# CAN_SN65HVD230D.net
KiCad netlist of a schematic drawn in Altium Designer
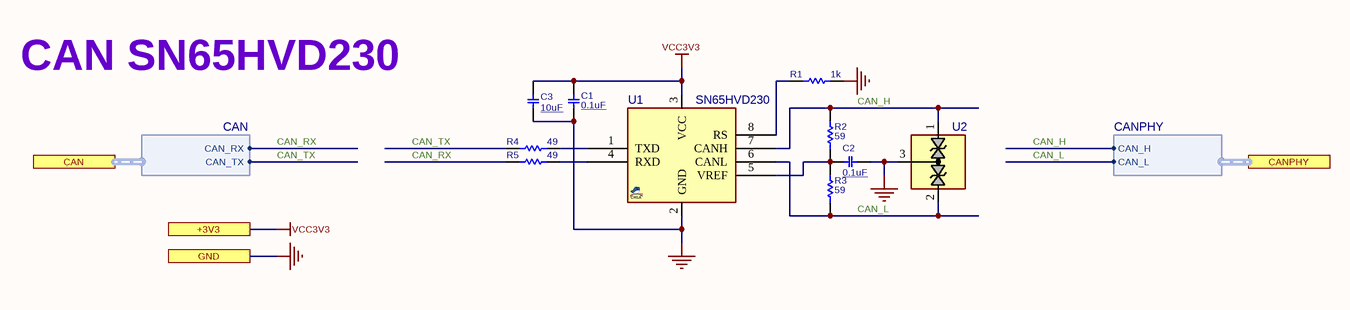
[diagram p0: CAN_SN65HVD230D.SchDoc]

(export (version "E")
  (design (tool "Eeschema 10.0.6"))
  (components
    (comp (ref "C1")
      (value "0.1uF")
      (footprint "C0603")
      (description "CAP, MLCC")
      (fields (field (name "MANF_P#") "MANF_PART#"))
      (libsource (lib "passive_smd") (part "CAP_SMD_MLCC_0402"))
    )
    (comp (ref "C2")
      (value "0.1uF")
      (footprint "C0603")
      (description "CAP, MLCC")
      (fields (field (name "MANF_P#") "MANF_PART#"))
      (libsource (lib "passive_smd") (part "CAP_SMD_MLCC_0402"))
    )
    (comp (ref "C3")
      (value "10uF")
      (footprint "C0603")
      (description "CAP, MLCC")
      (fields (field (name "MANF_P#") "MANF_PART#"))
      (libsource (lib "passive_smd") (part "CAP_SMD_MLCC_0402"))
    )
    (comp (ref "R1")
      (value "1k")
      (footprint "R0603")
      (description "RESISTOR, SMD")
      (libsource (lib "passive_smd") (part "RES_SMD_0402"))
    )
    (comp (ref "R2")
      (value "59")
      (footprint "R0603")
      (description "RESISTOR, SMD")
      (libsource (lib "passive_smd") (part "RES_SMD_0402"))
    )
    (comp (ref "R3")
      (value "59")
      (footprint "R0603")
      (description "RESISTOR, SMD")
      (libsource (lib "passive_smd") (part "RES_SMD_0402"))
    )
    (comp (ref "R4")
      (value "49")
      (footprint "R0603")
      (description "RESISTOR, SMD")
      (libsource (lib "passive_smd") (part "RES_SMD_0402"))
    )
    (comp (ref "R5")
      (value "49")
      (footprint "R0603")
      (description "RESISTOR, SMD")
      (libsource (lib "passive_smd") (part "RES_SMD_0402"))
    )
    (comp (ref "U1")
      (value "SN65HVD230")
      (footprint "SO_8")
      (description "CAN,  Transceivers, 3.3V (VDD)")
      (fields (field (name "MANF") "Texas Instruments") (field (name "MANF_P#") "SN65HVD230D, SN65HVD230QD"))
      (libsource (lib "can_phy") (part "SN65HVD230_SOP8"))
    )
    (comp (ref "U2")
      (value "CDSOT23-SM712")
      (footprint "SOT23_3")
      (description "TVS, ESD PROTECT, 2CH, 400W/17A PP, 7.5VBR, ±8KV ESDmin")
      (fields (field (name "MANF") "Bourns"))
      (libsource (lib "protect_tvs_esd_fuse") (part "TVS_X2_CDSOT23-SM712"))
    )
  )
  (nets
    (net (code "3") (name "/CAN_H") (class "Default")
      (node (ref "R2") (pin "2") (pinfunction "2_2") (pintype "passive"))
      (node (ref "U1") (pin "7") (pinfunction "CANH_7") (pintype "passive"))
      (node (ref "U2") (pin "1") (pinfunction "NC_1") (pintype "passive"))
    )
    (net (code "4") (name "/CAN_L") (class "Default")
      (node (ref "R3") (pin "1") (pinfunction "1_1") (pintype "passive"))
      (node (ref "U1") (pin "6") (pinfunction "CANL_6") (pintype "passive"))
      (node (ref "U2") (pin "2") (pinfunction "GND_2") (pintype "passive"))
    )
    (net (code "5") (name "/CAN_RX") (class "Default")
      (node (ref "R5") (pin "2") (pinfunction "2_2") (pintype "passive"))
    )
    (net (code "6") (name "/CAN_TX") (class "Default")
      (node (ref "R4") (pin "2") (pinfunction "2_2") (pintype "passive"))
    )
    (net (code "9") (name "GND") (class "Default")
      (node (ref "C1") (pin "1") (pinfunction "1_1") (pintype "passive"))
      (node (ref "C2") (pin "1") (pinfunction "1_1") (pintype "passive"))
      (node (ref "C3") (pin "2") (pinfunction "2_2") (pintype "passive"))
      (node (ref "R1") (pin "1") (pinfunction "1_1") (pintype "passive"))
      (node (ref "U1") (pin "2") (pinfunction "GND_2") (pintype "passive"))
      (node (ref "U2") (pin "3") (pinfunction "NC_3") (pintype "passive"))
    )
    (net (code "10") (name "Net-(U1-RS)") (class "Default")
      (node (ref "R1") (pin "2") (pinfunction "2_2") (pintype "passive"))
      (node (ref "U1") (pin "8") (pinfunction "RS_8") (pintype "passive"))
    )
    (net (code "11") (name "Net-(U1-RXD)") (class "Default")
      (node (ref "R5") (pin "1") (pinfunction "1_1") (pintype "passive"))
      (node (ref "U1") (pin "4") (pinfunction "RXD_4") (pintype "passive"))
    )
    (net (code "12") (name "Net-(U1-TXD)") (class "Default")
      (node (ref "R4") (pin "1") (pinfunction "1_1") (pintype "passive"))
      (node (ref "U1") (pin "1") (pinfunction "TXD_1") (pintype "passive"))
    )
    (net (code "13") (name "Net-(U1-VREF)") (class "Default")
      (node (ref "C2") (pin "2") (pinfunction "2_2") (pintype "passive"))
      (node (ref "R2") (pin "1") (pinfunction "1_1") (pintype "passive"))
      (node (ref "R3") (pin "2") (pinfunction "2_2") (pintype "passive"))
      (node (ref "U1") (pin "5") (pinfunction "VREF_5") (pintype "passive"))
    )
    (net (code "14") (name "VCC3V3") (class "Default")
      (node (ref "C1") (pin "2") (pinfunction "2_2") (pintype "passive"))
      (node (ref "C3") (pin "1") (pinfunction "1_1") (pintype "passive"))
      (node (ref "U1") (pin "3") (pinfunction "VCC_3") (pintype "passive"))
    )
  )
)
